# SMR.net
KiCad netlist of a schematic drawn in EAGLE
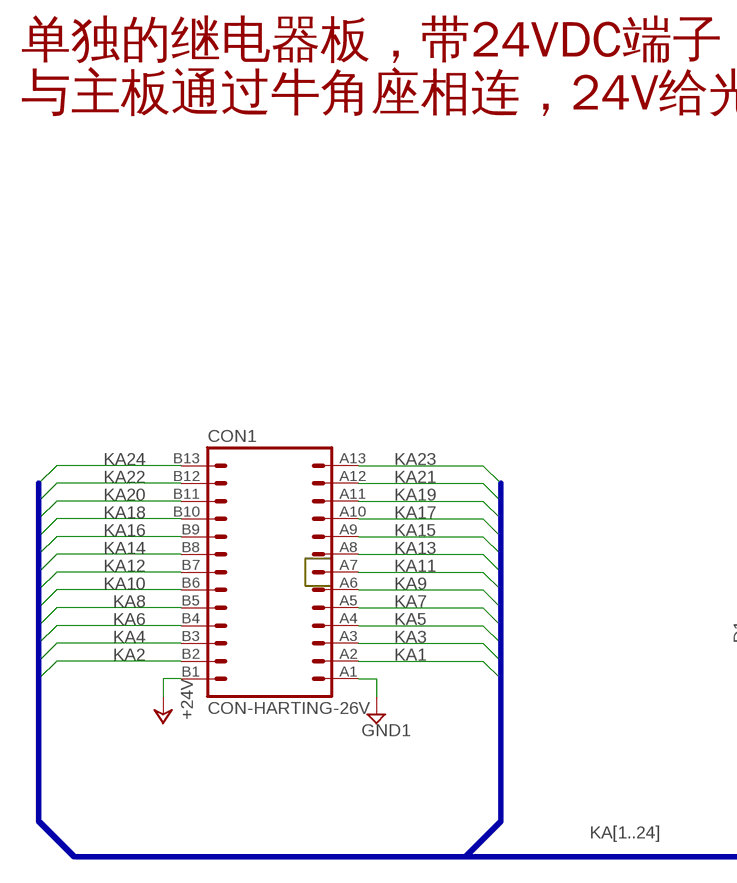
[diagram p0: schematic, sheet 1, part 1 of 2]
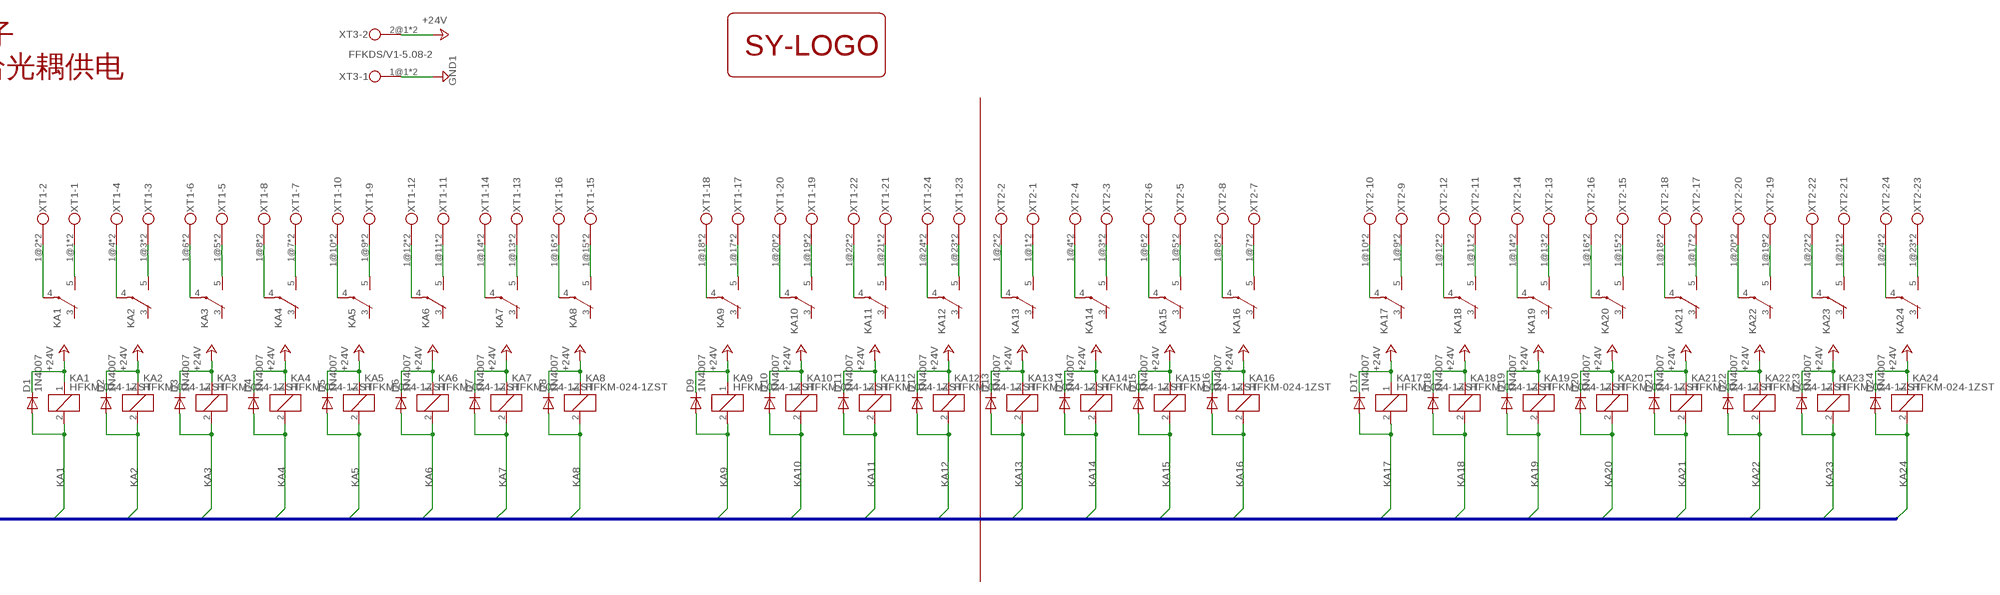
[diagram p1: schematic, sheet 1, part 2 of 2]

(export (version "E")
  (design (tool "Eeschema 10.0.6"))
  (components
    (comp (ref "CON1")
      (value "CON-HARTING-26V")
      (footprint "eagle-import:26V")
      (libsource (lib "eagle-import") (part "CON-HARTING-26V"))
    )
    (comp (ref "D1")
      (value "1N4007")
      (footprint "eagle-import:DO41-10")
      (libsource (lib "eagle-import") (part "1N4007"))
    )
    (comp (ref "D2")
      (value "1N4007")
      (footprint "eagle-import:DO41-10")
      (libsource (lib "eagle-import") (part "1N4007"))
    )
    (comp (ref "D3")
      (value "1N4007")
      (footprint "eagle-import:DO41-10")
      (libsource (lib "eagle-import") (part "1N4007"))
    )
    (comp (ref "D4")
      (value "1N4007")
      (footprint "eagle-import:DO41-10")
      (libsource (lib "eagle-import") (part "1N4007"))
    )
    (comp (ref "D5")
      (value "1N4007")
      (footprint "eagle-import:DO41-10")
      (libsource (lib "eagle-import") (part "1N4007"))
    )
    (comp (ref "D6")
      (value "1N4007")
      (footprint "eagle-import:DO41-10")
      (libsource (lib "eagle-import") (part "1N4007"))
    )
    (comp (ref "D7")
      (value "1N4007")
      (footprint "eagle-import:DO41-10")
      (libsource (lib "eagle-import") (part "1N4007"))
    )
    (comp (ref "D8")
      (value "1N4007")
      (footprint "eagle-import:DO41-10")
      (libsource (lib "eagle-import") (part "1N4007"))
    )
    (comp (ref "D9")
      (value "1N4007")
      (footprint "eagle-import:DO41-10")
      (libsource (lib "eagle-import") (part "1N4007"))
    )
    (comp (ref "D10")
      (value "1N4007")
      (footprint "eagle-import:DO41-10")
      (libsource (lib "eagle-import") (part "1N4007"))
    )
    (comp (ref "D11")
      (value "1N4007")
      (footprint "eagle-import:DO41-10")
      (libsource (lib "eagle-import") (part "1N4007"))
    )
    (comp (ref "D12")
      (value "1N4007")
      (footprint "eagle-import:DO41-10")
      (libsource (lib "eagle-import") (part "1N4007"))
    )
    (comp (ref "D13")
      (value "1N4007")
      (footprint "eagle-import:DO41-10")
      (libsource (lib "eagle-import") (part "1N4007"))
    )
    (comp (ref "D14")
      (value "1N4007")
      (footprint "eagle-import:DO41-10")
      (libsource (lib "eagle-import") (part "1N4007"))
    )
    (comp (ref "D15")
      (value "1N4007")
      (footprint "eagle-import:DO41-10")
      (libsource (lib "eagle-import") (part "1N4007"))
    )
    (comp (ref "D16")
      (value "1N4007")
      (footprint "eagle-import:DO41-10")
      (libsource (lib "eagle-import") (part "1N4007"))
    )
    (comp (ref "D17")
      (value "1N4007")
      (footprint "eagle-import:DO41-10")
      (libsource (lib "eagle-import") (part "1N4007"))
    )
    (comp (ref "D18")
      (value "1N4007")
      (footprint "eagle-import:DO41-10")
      (libsource (lib "eagle-import") (part "1N4007"))
    )
    (comp (ref "D19")
      (value "1N4007")
      (footprint "eagle-import:DO41-10")
      (libsource (lib "eagle-import") (part "1N4007"))
    )
    (comp (ref "D20")
      (value "1N4007")
      (footprint "eagle-import:DO41-10")
      (libsource (lib "eagle-import") (part "1N4007"))
    )
    (comp (ref "D21")
      (value "1N4007")
      (footprint "eagle-import:DO41-10")
      (libsource (lib "eagle-import") (part "1N4007"))
    )
    (comp (ref "D22")
      (value "1N4007")
      (footprint "eagle-import:DO41-10")
      (libsource (lib "eagle-import") (part "1N4007"))
    )
    (comp (ref "D23")
      (value "1N4007")
      (footprint "eagle-import:DO41-10")
      (libsource (lib "eagle-import") (part "1N4007"))
    )
    (comp (ref "D24")
      (value "1N4007")
      (footprint "eagle-import:DO41-10")
      (libsource (lib "eagle-import") (part "1N4007"))
    )
    (comp (ref "KA1")
      (value "HFKM-024-1ZST")
      (footprint "eagle-import:HFKM-1ZST")
      (libsource (lib "eagle-import") (part "HFKM-024-1ZST"))
    )
    (comp (ref "KA2")
      (value "HFKM-024-1ZST")
      (footprint "eagle-import:HFKM-1ZST")
      (libsource (lib "eagle-import") (part "HFKM-024-1ZST"))
    )
    (comp (ref "KA3")
      (value "HFKM-024-1ZST")
      (footprint "eagle-import:HFKM-1ZST")
      (libsource (lib "eagle-import") (part "HFKM-024-1ZST"))
    )
    (comp (ref "KA4")
      (value "HFKM-024-1ZST")
      (footprint "eagle-import:HFKM-1ZST")
      (libsource (lib "eagle-import") (part "HFKM-024-1ZST"))
    )
    (comp (ref "KA5")
      (value "HFKM-024-1ZST")
      (footprint "eagle-import:HFKM-1ZST")
      (libsource (lib "eagle-import") (part "HFKM-024-1ZST"))
    )
    (comp (ref "KA6")
      (value "HFKM-024-1ZST")
      (footprint "eagle-import:HFKM-1ZST")
      (libsource (lib "eagle-import") (part "HFKM-024-1ZST"))
    )
    (comp (ref "KA7")
      (value "HFKM-024-1ZST")
      (footprint "eagle-import:HFKM-1ZST")
      (libsource (lib "eagle-import") (part "HFKM-024-1ZST"))
    )
    (comp (ref "KA8")
      (value "HFKM-024-1ZST")
      (footprint "eagle-import:HFKM-1ZST")
      (libsource (lib "eagle-import") (part "HFKM-024-1ZST"))
    )
    (comp (ref "KA9")
      (value "HFKM-024-1ZST")
      (footprint "eagle-import:HFKM-1ZST")
      (libsource (lib "eagle-import") (part "HFKM-024-1ZST"))
    )
    (comp (ref "KA10")
      (value "HFKM-024-1ZST")
      (footprint "eagle-import:HFKM-1ZST")
      (libsource (lib "eagle-import") (part "HFKM-024-1ZST"))
    )
    (comp (ref "KA11")
      (value "HFKM-024-1ZST")
      (footprint "eagle-import:HFKM-1ZST")
      (libsource (lib "eagle-import") (part "HFKM-024-1ZST"))
    )
    (comp (ref "KA12")
      (value "HFKM-024-1ZST")
      (footprint "eagle-import:HFKM-1ZST")
      (libsource (lib "eagle-import") (part "HFKM-024-1ZST"))
    )
    (comp (ref "KA13")
      (value "HFKM-024-1ZST")
      (footprint "eagle-import:HFKM-1ZST")
      (libsource (lib "eagle-import") (part "HFKM-024-1ZST"))
    )
    (comp (ref "KA14")
      (value "HFKM-024-1ZST")
      (footprint "eagle-import:HFKM-1ZST")
      (libsource (lib "eagle-import") (part "HFKM-024-1ZST"))
    )
    (comp (ref "KA15")
      (value "HFKM-024-1ZST")
      (footprint "eagle-import:HFKM-1ZST")
      (libsource (lib "eagle-import") (part "HFKM-024-1ZST"))
    )
    (comp (ref "KA16")
      (value "HFKM-024-1ZST")
      (footprint "eagle-import:HFKM-1ZST")
      (libsource (lib "eagle-import") (part "HFKM-024-1ZST"))
    )
    (comp (ref "KA17")
      (value "HFKM-024-1ZST")
      (footprint "eagle-import:HFKM-1ZST")
      (libsource (lib "eagle-import") (part "HFKM-024-1ZST"))
    )
    (comp (ref "KA18")
      (value "HFKM-024-1ZST")
      (footprint "eagle-import:HFKM-1ZST")
      (libsource (lib "eagle-import") (part "HFKM-024-1ZST"))
    )
    (comp (ref "KA19")
      (value "HFKM-024-1ZST")
      (footprint "eagle-import:HFKM-1ZST")
      (libsource (lib "eagle-import") (part "HFKM-024-1ZST"))
    )
    (comp (ref "KA20")
      (value "HFKM-024-1ZST")
      (footprint "eagle-import:HFKM-1ZST")
      (libsource (lib "eagle-import") (part "HFKM-024-1ZST"))
    )
    (comp (ref "KA21")
      (value "HFKM-024-1ZST")
      (footprint "eagle-import:HFKM-1ZST")
      (libsource (lib "eagle-import") (part "HFKM-024-1ZST"))
    )
    (comp (ref "KA22")
      (value "HFKM-024-1ZST")
      (footprint "eagle-import:HFKM-1ZST")
      (libsource (lib "eagle-import") (part "HFKM-024-1ZST"))
    )
    (comp (ref "KA23")
      (value "HFKM-024-1ZST")
      (footprint "eagle-import:HFKM-1ZST")
      (libsource (lib "eagle-import") (part "HFKM-024-1ZST"))
    )
    (comp (ref "KA24")
      (value "HFKM-024-1ZST")
      (footprint "eagle-import:HFKM-1ZST")
      (libsource (lib "eagle-import") (part "HFKM-024-1ZST"))
    )
    (comp (ref "LOGO1")
      (value "SY-LOGO_BOTTOM")
      (footprint "eagle-import:SY-LOGO_BOTTOM")
      (libsource (lib "eagle-import") (part "SY-LOGO_BOTTOM"))
    )
    (comp (ref "XT1")
      (value "FFKDS/V1-5.08-24")
      (footprint "eagle-import:FFKDS_V1-5.08-24")
      (libsource (lib "eagle-import") (part "FFKDS/V1-5.08-24"))
    )
    (comp (ref "XT2")
      (value "FFKDS/V1-5.08-24")
      (footprint "eagle-import:FFKDS_V1-5.08-24")
      (libsource (lib "eagle-import") (part "FFKDS/V1-5.08-24"))
    )
    (comp (ref "XT3")
      (value "FFKDS/V1-5.08-2")
      (footprint "eagle-import:FFKDS_V1-5.08-2")
      (libsource (lib "eagle-import") (part "FFKDS/V1-5.08-2"))
    )
  )
  (nets
    (net (code "1") (name "+24V") (class "Default")
      (node (ref "CON1") (pin "B1") (pinfunction "B1_B1") (pintype "passive"))
      (node (ref "D1") (pin "C") (pinfunction "C_C") (pintype "passive"))
      (node (ref "D10") (pin "C") (pinfunction "C_C") (pintype "passive"))
      (node (ref "D11") (pin "C") (pinfunction "C_C") (pintype "passive"))
      (node (ref "D12") (pin "C") (pinfunction "C_C") (pintype "passive"))
      (node (ref "D13") (pin "C") (pinfunction "C_C") (pintype "passive"))
      (node (ref "D14") (pin "C") (pinfunction "C_C") (pintype "passive"))
      (node (ref "D15") (pin "C") (pinfunction "C_C") (pintype "passive"))
      (node (ref "D16") (pin "C") (pinfunction "C_C") (pintype "passive"))
      (node (ref "D17") (pin "C") (pinfunction "C_C") (pintype "passive"))
      (node (ref "D18") (pin "C") (pinfunction "C_C") (pintype "passive"))
      (node (ref "D19") (pin "C") (pinfunction "C_C") (pintype "passive"))
      (node (ref "D2") (pin "C") (pinfunction "C_C") (pintype "passive"))
      (node (ref "D20") (pin "C") (pinfunction "C_C") (pintype "passive"))
      (node (ref "D21") (pin "C") (pinfunction "C_C") (pintype "passive"))
      (node (ref "D22") (pin "C") (pinfunction "C_C") (pintype "passive"))
      (node (ref "D23") (pin "C") (pinfunction "C_C") (pintype "passive"))
      (node (ref "D24") (pin "C") (pinfunction "C_C") (pintype "passive"))
      (node (ref "D3") (pin "C") (pinfunction "C_C") (pintype "passive"))
      (node (ref "D4") (pin "C") (pinfunction "C_C") (pintype "passive"))
      (node (ref "D5") (pin "C") (pinfunction "C_C") (pintype "passive"))
      (node (ref "D6") (pin "C") (pinfunction "C_C") (pintype "passive"))
      (node (ref "D7") (pin "C") (pinfunction "C_C") (pintype "passive"))
      (node (ref "D8") (pin "C") (pinfunction "C_C") (pintype "passive"))
      (node (ref "D9") (pin "C") (pinfunction "C_C") (pintype "passive"))
      (node (ref "KA1") (pin "1") (pinfunction "COIL1_1") (pintype "passive"))
      (node (ref "KA10") (pin "1") (pinfunction "COIL1_1") (pintype "passive"))
      (node (ref "KA11") (pin "1") (pinfunction "COIL1_1") (pintype "passive"))
      (node (ref "KA12") (pin "1") (pinfunction "COIL1_1") (pintype "passive"))
      (node (ref "KA13") (pin "1") (pinfunction "COIL1_1") (pintype "passive"))
      (node (ref "KA14") (pin "1") (pinfunction "COIL1_1") (pintype "passive"))
      (node (ref "KA15") (pin "1") (pinfunction "COIL1_1") (pintype "passive"))
      (node (ref "KA16") (pin "1") (pinfunction "COIL1_1") (pintype "passive"))
      (node (ref "KA17") (pin "1") (pinfunction "COIL1_1") (pintype "passive"))
      (node (ref "KA18") (pin "1") (pinfunction "COIL1_1") (pintype "passive"))
      (node (ref "KA19") (pin "1") (pinfunction "COIL1_1") (pintype "passive"))
      (node (ref "KA2") (pin "1") (pinfunction "COIL1_1") (pintype "passive"))
      (node (ref "KA20") (pin "1") (pinfunction "COIL1_1") (pintype "passive"))
      (node (ref "KA21") (pin "1") (pinfunction "COIL1_1") (pintype "passive"))
      (node (ref "KA22") (pin "1") (pinfunction "COIL1_1") (pintype "passive"))
      (node (ref "KA23") (pin "1") (pinfunction "COIL1_1") (pintype "passive"))
      (node (ref "KA24") (pin "1") (pinfunction "COIL1_1") (pintype "passive"))
      (node (ref "KA3") (pin "1") (pinfunction "COIL1_1") (pintype "passive"))
      (node (ref "KA4") (pin "1") (pinfunction "COIL1_1") (pintype "passive"))
      (node (ref "KA5") (pin "1") (pinfunction "COIL1_1") (pintype "passive"))
      (node (ref "KA6") (pin "1") (pinfunction "COIL1_1") (pintype "passive"))
      (node (ref "KA7") (pin "1") (pinfunction "COIL1_1") (pintype "passive"))
      (node (ref "KA8") (pin "1") (pinfunction "COIL1_1") (pintype "passive"))
      (node (ref "KA9") (pin "1") (pinfunction "COIL1_1") (pintype "passive"))
      (node (ref "XT3") (pin "2@1") (pinfunction "1_2@1") (pintype "passive"))
      (node (ref "XT3") (pin "2@2") (pinfunction "1_2@2") (pintype "passive"))
    )
    (net (code "2") (name "/KA1") (class "Default")
      (node (ref "CON1") (pin "A2") (pinfunction "A2_A2") (pintype "passive"))
      (node (ref "D1") (pin "A") (pinfunction "A_A") (pintype "passive"))
      (node (ref "KA1") (pin "2") (pinfunction "COIL2_2") (pintype "passive"))
    )
    (net (code "3") (name "/KA2") (class "Default")
      (node (ref "CON1") (pin "B2") (pinfunction "B2_B2") (pintype "passive"))
      (node (ref "D2") (pin "A") (pinfunction "A_A") (pintype "passive"))
      (node (ref "KA2") (pin "2") (pinfunction "COIL2_2") (pintype "passive"))
    )
    (net (code "4") (name "/KA3") (class "Default")
      (node (ref "CON1") (pin "A3") (pinfunction "A3_A3") (pintype "passive"))
      (node (ref "D3") (pin "A") (pinfunction "A_A") (pintype "passive"))
      (node (ref "KA3") (pin "2") (pinfunction "COIL2_2") (pintype "passive"))
    )
    (net (code "5") (name "/KA4") (class "Default")
      (node (ref "CON1") (pin "B3") (pinfunction "B3_B3") (pintype "passive"))
      (node (ref "D4") (pin "A") (pinfunction "A_A") (pintype "passive"))
      (node (ref "KA4") (pin "2") (pinfunction "COIL2_2") (pintype "passive"))
    )
    (net (code "6") (name "/KA5") (class "Default")
      (node (ref "CON1") (pin "A4") (pinfunction "A4_A4") (pintype "passive"))
      (node (ref "D5") (pin "A") (pinfunction "A_A") (pintype "passive"))
      (node (ref "KA5") (pin "2") (pinfunction "COIL2_2") (pintype "passive"))
    )
    (net (code "7") (name "/KA6") (class "Default")
      (node (ref "CON1") (pin "B4") (pinfunction "B4_B4") (pintype "passive"))
      (node (ref "D6") (pin "A") (pinfunction "A_A") (pintype "passive"))
      (node (ref "KA6") (pin "2") (pinfunction "COIL2_2") (pintype "passive"))
    )
    (net (code "8") (name "/KA7") (class "Default")
      (node (ref "CON1") (pin "A5") (pinfunction "A5_A5") (pintype "passive"))
      (node (ref "D7") (pin "A") (pinfunction "A_A") (pintype "passive"))
      (node (ref "KA7") (pin "2") (pinfunction "COIL2_2") (pintype "passive"))
    )
    (net (code "9") (name "/KA8") (class "Default")
      (node (ref "CON1") (pin "B5") (pinfunction "B5_B5") (pintype "passive"))
      (node (ref "D8") (pin "A") (pinfunction "A_A") (pintype "passive"))
      (node (ref "KA8") (pin "2") (pinfunction "COIL2_2") (pintype "passive"))
    )
    (net (code "10") (name "/KA9") (class "Default")
      (node (ref "CON1") (pin "A6") (pinfunction "A6_A6") (pintype "passive"))
      (node (ref "D9") (pin "A") (pinfunction "A_A") (pintype "passive"))
      (node (ref "KA9") (pin "2") (pinfunction "COIL2_2") (pintype "passive"))
    )
    (net (code "11") (name "/KA10") (class "Default")
      (node (ref "CON1") (pin "B6") (pinfunction "B6_B6") (pintype "passive"))
      (node (ref "D10") (pin "A") (pinfunction "A_A") (pintype "passive"))
      (node (ref "KA10") (pin "2") (pinfunction "COIL2_2") (pintype "passive"))
    )
    (net (code "12") (name "/KA11") (class "Default")
      (node (ref "CON1") (pin "A7") (pinfunction "A7_A7") (pintype "passive"))
      (node (ref "D11") (pin "A") (pinfunction "A_A") (pintype "passive"))
      (node (ref "KA11") (pin "2") (pinfunction "COIL2_2") (pintype "passive"))
    )
    (net (code "13") (name "/KA12") (class "Default")
      (node (ref "CON1") (pin "B7") (pinfunction "B7_B7") (pintype "passive"))
      (node (ref "D12") (pin "A") (pinfunction "A_A") (pintype "passive"))
      (node (ref "KA12") (pin "2") (pinfunction "COIL2_2") (pintype "passive"))
    )
    (net (code "14") (name "/KA13") (class "Default")
      (node (ref "CON1") (pin "A8") (pinfunction "A8_A8") (pintype "passive"))
      (node (ref "D13") (pin "A") (pinfunction "A_A") (pintype "passive"))
      (node (ref "KA13") (pin "2") (pinfunction "COIL2_2") (pintype "passive"))
    )
    (net (code "15") (name "/KA14") (class "Default")
      (node (ref "CON1") (pin "B8") (pinfunction "B8_B8") (pintype "passive"))
      (node (ref "D14") (pin "A") (pinfunction "A_A") (pintype "passive"))
      (node (ref "KA14") (pin "2") (pinfunction "COIL2_2") (pintype "passive"))
    )
    (net (code "16") (name "/KA15") (class "Default")
      (node (ref "CON1") (pin "A9") (pinfunction "A9_A9") (pintype "passive"))
      (node (ref "D15") (pin "A") (pinfunction "A_A") (pintype "passive"))
      (node (ref "KA15") (pin "2") (pinfunction "COIL2_2") (pintype "passive"))
    )
    (net (code "17") (name "/KA16") (class "Default")
      (node (ref "CON1") (pin "B9") (pinfunction "B9_B9") (pintype "passive"))
      (node (ref "D16") (pin "A") (pinfunction "A_A") (pintype "passive"))
      (node (ref "KA16") (pin "2") (pinfunction "COIL2_2") (pintype "passive"))
    )
    (net (code "18") (name "/KA17") (class "Default")
      (node (ref "CON1") (pin "A10") (pinfunction "A10_A10") (pintype "passive"))
      (node (ref "D17") (pin "A") (pinfunction "A_A") (pintype "passive"))
      (node (ref "KA17") (pin "2") (pinfunction "COIL2_2") (pintype "passive"))
    )
    (net (code "19") (name "/KA18") (class "Default")
      (node (ref "CON1") (pin "B10") (pinfunction "B10_B10") (pintype "passive"))
      (node (ref "D18") (pin "A") (pinfunction "A_A") (pintype "passive"))
      (node (ref "KA18") (pin "2") (pinfunction "COIL2_2") (pintype "passive"))
    )
    (net (code "20") (name "/KA19") (class "Default")
      (node (ref "CON1") (pin "A11") (pinfunction "A11_A11") (pintype "passive"))
      (node (ref "D19") (pin "A") (pinfunction "A_A") (pintype "passive"))
      (node (ref "KA19") (pin "2") (pinfunction "COIL2_2") (pintype "passive"))
    )
    (net (code "21") (name "/KA20") (class "Default")
      (node (ref "CON1") (pin "B11") (pinfunction "B11_B11") (pintype "passive"))
      (node (ref "D20") (pin "A") (pinfunction "A_A") (pintype "passive"))
      (node (ref "KA20") (pin "2") (pinfunction "COIL2_2") (pintype "passive"))
    )
    (net (code "22") (name "/KA21") (class "Default")
      (node (ref "CON1") (pin "A12") (pinfunction "A12_A12") (pintype "passive"))
      (node (ref "D21") (pin "A") (pinfunction "A_A") (pintype "passive"))
      (node (ref "KA21") (pin "2") (pinfunction "COIL2_2") (pintype "passive"))
    )
    (net (code "23") (name "/KA22") (class "Default")
      (node (ref "CON1") (pin "B12") (pinfunction "B12_B12") (pintype "passive"))
      (node (ref "D22") (pin "A") (pinfunction "A_A") (pintype "passive"))
      (node (ref "KA22") (pin "2") (pinfunction "COIL2_2") (pintype "passive"))
    )
    (net (code "24") (name "/KA23") (class "Default")
      (node (ref "CON1") (pin "A13") (pinfunction "A13_A13") (pintype "passive"))
      (node (ref "D23") (pin "A") (pinfunction "A_A") (pintype "passive"))
      (node (ref "KA23") (pin "2") (pinfunction "COIL2_2") (pintype "passive"))
    )
    (net (code "25") (name "/KA24") (class "Default")
      (node (ref "CON1") (pin "B13") (pinfunction "B13_B13") (pintype "passive"))
      (node (ref "D24") (pin "A") (pinfunction "A_A") (pintype "passive"))
      (node (ref "KA24") (pin "2") (pinfunction "COIL2_2") (pintype "passive"))
    )
    (net (code "27") (name "GND1") (class "Default")
      (node (ref "CON1") (pin "A1") (pinfunction "A1_A1") (pintype "passive"))
      (node (ref "XT3") (pin "1@1") (pinfunction "1_1@1") (pintype "passive"))
      (node (ref "XT3") (pin "1@2") (pinfunction "1_1@2") (pintype "passive"))
    )
    (net (code "28") (name "Net-(KA1B-COM)") (class "Default")
      (node (ref "KA1") (pin "4") (pinfunction "COM_4") (pintype "passive"))
      (node (ref "XT1") (pin "1@2") (pinfunction "1_1@2") (pintype "passive"))
      (node (ref "XT1") (pin "2@2") (pinfunction "1_2@2") (pintype "passive"))
    )
    (net (code "29") (name "Net-(KA1B-NO)") (class "Default")
      (node (ref "KA1") (pin "5") (pinfunction "NO_5") (pintype "passive"))
      (node (ref "XT1") (pin "1@1") (pinfunction "1_1@1") (pintype "passive"))
      (node (ref "XT1") (pin "2@1") (pinfunction "1_2@1") (pintype "passive"))
    )
    (net (code "30") (name "Net-(KA2B-COM)") (class "Default")
      (node (ref "KA2") (pin "4") (pinfunction "COM_4") (pintype "passive"))
      (node (ref "XT1") (pin "1@4") (pinfunction "1_1@4") (pintype "passive"))
      (node (ref "XT1") (pin "2@4") (pinfunction "1_2@4") (pintype "passive"))
    )
    (net (code "31") (name "Net-(KA2B-NO)") (class "Default")
      (node (ref "KA2") (pin "5") (pinfunction "NO_5") (pintype "passive"))
      (node (ref "XT1") (pin "1@3") (pinfunction "1_1@3") (pintype "passive"))
      (node (ref "XT1") (pin "2@3") (pinfunction "1_2@3") (pintype "passive"))
    )
    (net (code "32") (name "Net-(KA3B-COM)") (class "Default")
      (node (ref "KA3") (pin "4") (pinfunction "COM_4") (pintype "passive"))
      (node (ref "XT1") (pin "1@6") (pinfunction "1_1@6") (pintype "passive"))
      (node (ref "XT1") (pin "2@6") (pinfunction "1_2@6") (pintype "passive"))
    )
    (net (code "33") (name "Net-(KA3B-NO)") (class "Default")
      (node (ref "KA3") (pin "5") (pinfunction "NO_5") (pintype "passive"))
      (node (ref "XT1") (pin "1@5") (pinfunction "1_1@5") (pintype "passive"))
      (node (ref "XT1") (pin "2@5") (pinfunction "1_2@5") (pintype "passive"))
    )
    (net (code "34") (name "Net-(KA4B-COM)") (class "Default")
      (node (ref "KA4") (pin "4") (pinfunction "COM_4") (pintype "passive"))
      (node (ref "XT1") (pin "1@8") (pinfunction "1_1@8") (pintype "passive"))
      (node (ref "XT1") (pin "2@8") (pinfunction "1_2@8") (pintype "passive"))
    )
    (net (code "35") (name "Net-(KA4B-NO)") (class "Default")
      (node (ref "KA4") (pin "5") (pinfunction "NO_5") (pintype "passive"))
      (node (ref "XT1") (pin "1@7") (pinfunction "1_1@7") (pintype "passive"))
      (node (ref "XT1") (pin "2@7") (pinfunction "1_2@7") (pintype "passive"))
    )
    (net (code "36") (name "Net-(KA5B-COM)") (class "Default")
      (node (ref "KA5") (pin "4") (pinfunction "COM_4") (pintype "passive"))
      (node (ref "XT1") (pin "1@10") (pinfunction "1_1@10") (pintype "passive"))
      (node (ref "XT1") (pin "2@10") (pinfunction "1_2@10") (pintype "passive"))
    )
    (net (code "37") (name "Net-(KA5B-NO)") (class "Default")
      (node (ref "KA5") (pin "5") (pinfunction "NO_5") (pintype "passive"))
      (node (ref "XT1") (pin "1@9") (pinfunction "1_1@9") (pintype "passive"))
      (node (ref "XT1") (pin "2@9") (pinfunction "1_2@9") (pintype "passive"))
    )
    (net (code "38") (name "Net-(KA6B-COM)") (class "Default")
      (node (ref "KA6") (pin "4") (pinfunction "COM_4") (pintype "passive"))
      (node (ref "XT1") (pin "1@12") (pinfunction "1_1@12") (pintype "passive"))
      (node (ref "XT1") (pin "2@12") (pinfunction "1_2@12") (pintype "passive"))
    )
    (net (code "39") (name "Net-(KA6B-NO)") (class "Default")
      (node (ref "KA6") (pin "5") (pinfunction "NO_5") (pintype "passive"))
      (node (ref "XT1") (pin "1@11") (pinfunction "1_1@11") (pintype "passive"))
      (node (ref "XT1") (pin "2@11") (pinfunction "1_2@11") (pintype "passive"))
    )
    (net (code "40") (name "Net-(KA7B-COM)") (class "Default")
      (node (ref "KA7") (pin "4") (pinfunction "COM_4") (pintype "passive"))
      (node (ref "XT1") (pin "1@14") (pinfunction "1_1@14") (pintype "passive"))
      (node (ref "XT1") (pin "2@14") (pinfunction "1_2@14") (pintype "passive"))
    )
    (net (code "41") (name "Net-(KA7B-NO)") (class "Default")
      (node (ref "KA7") (pin "5") (pinfunction "NO_5") (pintype "passive"))
      (node (ref "XT1") (pin "1@13") (pinfunction "1_1@13") (pintype "passive"))
      (node (ref "XT1") (pin "2@13") (pinfunction "1_2@13") (pintype "passive"))
    )
    (net (code "42") (name "Net-(KA8B-COM)") (class "Default")
      (node (ref "KA8") (pin "4") (pinfunction "COM_4") (pintype "passive"))
      (node (ref "XT1") (pin "1@16") (pinfunction "1_1@16") (pintype "passive"))
      (node (ref "XT1") (pin "2@16") (pinfunction "1_2@16") (pintype "passive"))
    )
    (net (code "43") (name "Net-(KA8B-NO)") (class "Default")
      (node (ref "KA8") (pin "5") (pinfunction "NO_5") (pintype "passive"))
      (node (ref "XT1") (pin "1@15") (pinfunction "1_1@15") (pintype "passive"))
      (node (ref "XT1") (pin "2@15") (pinfunction "1_2@15") (pintype "passive"))
    )
    (net (code "44") (name "Net-(KA9B-COM)") (class "Default")
      (node (ref "KA9") (pin "4") (pinfunction "COM_4") (pintype "passive"))
      (node (ref "XT1") (pin "1@18") (pinfunction "1_1@18") (pintype "passive"))
      (node (ref "XT1") (pin "2@18") (pinfunction "1_2@18") (pintype "passive"))
    )
    (net (code "45") (name "Net-(KA9B-NO)") (class "Default")
      (node (ref "KA9") (pin "5") (pinfunction "NO_5") (pintype "passive"))
      (node (ref "XT1") (pin "1@17") (pinfunction "1_1@17") (pintype "passive"))
      (node (ref "XT1") (pin "2@17") (pinfunction "1_2@17") (pintype "passive"))
    )
    (net (code "46") (name "Net-(KA10B-COM)") (class "Default")
      (node (ref "KA10") (pin "4") (pinfunction "COM_4") (pintype "passive"))
      (node (ref "XT1") (pin "1@20") (pinfunction "1_1@20") (pintype "passive"))
      (node (ref "XT1") (pin "2@20") (pinfunction "1_2@20") (pintype "passive"))
    )
    (net (code "47") (name "Net-(KA10B-NO)") (class "Default")
      (node (ref "KA10") (pin "5") (pinfunction "NO_5") (pintype "passive"))
      (node (ref "XT1") (pin "1@19") (pinfunction "1_1@19") (pintype "passive"))
      (node (ref "XT1") (pin "2@19") (pinfunction "1_2@19") (pintype "passive"))
    )
    (net (code "48") (name "Net-(KA11B-COM)") (class "Default")
      (node (ref "KA11") (pin "4") (pinfunction "COM_4") (pintype "passive"))
      (node (ref "XT1") (pin "1@22") (pinfunction "1_1@22") (pintype "passive"))
      (node (ref "XT1") (pin "2@22") (pinfunction "1_2@22") (pintype "passive"))
    )
    (net (code "49") (name "Net-(KA11B-NO)") (class "Default")
      (node (ref "KA11") (pin "5") (pinfunction "NO_5") (pintype "passive"))
      (node (ref "XT1") (pin "1@21") (pinfunction "1_1@21") (pintype "passive"))
      (node (ref "XT1") (pin "2@21") (pinfunction "1_2@21") (pintype "passive"))
    )
    (net (code "50") (name "Net-(KA12B-COM)") (class "Default")
      (node (ref "KA12") (pin "4") (pinfunction "COM_4") (pintype "passive"))
      (node (ref "XT1") (pin "1@24") (pinfunction "1_1@24") (pintype "passive"))
      (node (ref "XT1") (pin "2@24") (pinfunction "1_2@24") (pintype "passive"))
    )
    (net (code "51") (name "Net-(KA12B-NO)") (class "Default")
      (node (ref "KA12") (pin "5") (pinfunction "NO_5") (pintype "passive"))
      (node (ref "XT1") (pin "1@23") (pinfunction "1_1@23") (pintype "passive"))
      (node (ref "XT1") (pin "2@23") (pinfunction "1_2@23") (pintype "passive"))
    )
    (net (code "52") (name "Net-(KA13B-COM)") (class "Default")
      (node (ref "KA13") (pin "4") (pinfunction "COM_4") (pintype "passive"))
      (node (ref "XT2") (pin "1@2") (pinfunction "1_1@2") (pintype "passive"))
      (node (ref "XT2") (pin "2@2") (pinfunction "1_2@2") (pintype "passive"))
    )
    (net (code "53") (name "Net-(KA13B-NO)") (class "Default")
      (node (ref "KA13") (pin "5") (pinfunction "NO_5") (pintype "passive"))
      (node (ref "XT2") (pin "1@1") (pinfunction "1_1@1") (pintype "passive"))
      (node (ref "XT2") (pin "2@1") (pinfunction "1_2@1") (pintype "passive"))
    )
    (net (code "54") (name "Net-(KA14B-COM)") (class "Default")
      (node (ref "KA14") (pin "4") (pinfunction "COM_4") (pintype "passive"))
      (node (ref "XT2") (pin "1@4") (pinfunction "1_1@4") (pintype "passive"))
      (node (ref "XT2") (pin "2@4") (pinfunction "1_2@4") (pintype "passive"))
    )
    (net (code "55") (name "Net-(KA14B-NO)") (class "Default")
      (node (ref "KA14") (pin "5") (pinfunction "NO_5") (pintype "passive"))
      (node (ref "XT2") (pin "1@3") (pinfunction "1_1@3") (pintype "passive"))
      (node (ref "XT2") (pin "2@3") (pinfunction "1_2@3") (pintype "passive"))
    )
    (net (code "56") (name "Net-(KA15B-COM)") (class "Default")
      (node (ref "KA15") (pin "4") (pinfunction "COM_4") (pintype "passive"))
      (node (ref "XT2") (pin "1@6") (pinfunction "1_1@6") (pintype "passive"))
      (node (ref "XT2") (pin "2@6") (pinfunction "1_2@6") (pintype "passive"))
    )
    (net (code "57") (name "Net-(KA15B-NO)") (class "Default")
      (node (ref "KA15") (pin "5") (pinfunction "NO_5") (pintype "passive"))
      (node (ref "XT2") (pin "1@5") (pinfunction "1_1@5") (pintype "passive"))
      (node (ref "XT2") (pin "2@5") (pinfunction "1_2@5") (pintype "passive"))
    )
    (net (code "58") (name "Net-(KA16B-COM)") (class "Default")
      (node (ref "KA16") (pin "4") (pinfunction "COM_4") (pintype "passive"))
      (node (ref "XT2") (pin "1@8") (pinfunction "1_1@8") (pintype "passive"))
      (node (ref "XT2") (pin "2@8") (pinfunction "1_2@8") (pintype "passive"))
    )
    (net (code "59") (name "Net-(KA16B-NO)") (class "Default")
      (node (ref "KA16") (pin "5") (pinfunction "NO_5") (pintype "passive"))
      (node (ref "XT2") (pin "1@7") (pinfunction "1_1@7") (pintype "passive"))
      (node (ref "XT2") (pin "2@7") (pinfunction "1_2@7") (pintype "passive"))
    )
    (net (code "60") (name "Net-(KA17B-COM)") (class "Default")
      (node (ref "KA17") (pin "4") (pinfunction "COM_4") (pintype "passive"))
      (node (ref "XT2") (pin "1@10") (pinfunction "1_1@10") (pintype "passive"))
      (node (ref "XT2") (pin "2@10") (pinfunction "1_2@10") (pintype "passive"))
    )
    (net (code "61") (name "Net-(KA17B-NO)") (class "Default")
      (node (ref "KA17") (pin "5") (pinfunction "NO_5") (pintype "passive"))
      (node (ref "XT2") (pin "1@9") (pinfunction "1_1@9") (pintype "passive"))
      (node (ref "XT2") (pin "2@9") (pinfunction "1_2@9") (pintype "passive"))
    )
    (net (code "62") (name "Net-(KA18B-COM)") (class "Default")
      (node (ref "KA18") (pin "4") (pinfunction "COM_4") (pintype "passive"))
      (node (ref "XT2") (pin "1@12") (pinfunction "1_1@12") (pintype "passive"))
      (node (ref "XT2") (pin "2@12") (pinfunction "1_2@12") (pintype "passive"))
    )
    (net (code "63") (name "Net-(KA18B-NO)") (class "Default")
      (node (ref "KA18") (pin "5") (pinfunction "NO_5") (pintype "passive"))
      (node (ref "XT2") (pin "1@11") (pinfunction "1_1@11") (pintype "passive"))
      (node (ref "XT2") (pin "2@11") (pinfunction "1_2@11") (pintype "passive"))
    )
    (net (code "64") (name "Net-(KA19B-COM)") (class "Default")
      (node (ref "KA19") (pin "4") (pinfunction "COM_4") (pintype "passive"))
      (node (ref "XT2") (pin "1@14") (pinfunction "1_1@14") (pintype "passive"))
      (node (ref "XT2") (pin "2@14") (pinfunction "1_2@14") (pintype "passive"))
    )
    (net (code "65") (name "Net-(KA19B-NO)") (class "Default")
      (node (ref "KA19") (pin "5") (pinfunction "NO_5") (pintype "passive"))
      (node (ref "XT2") (pin "1@13") (pinfunction "1_1@13") (pintype "passive"))
      (node (ref "XT2") (pin "2@13") (pinfunction "1_2@13") (pintype "passive"))
    )
    (net (code "66") (name "Net-(KA20B-COM)") (class "Default")
      (node (ref "KA20") (pin "4") (pinfunction "COM_4") (pintype "passive"))
      (node (ref "XT2") (pin "1@16") (pinfunction "1_1@16") (pintype "passive"))
      (node (ref "XT2") (pin "2@16") (pinfunction "1_2@16") (pintype "passive"))
    )
    (net (code "67") (name "Net-(KA20B-NO)") (class "Default")
      (node (ref "KA20") (pin "5") (pinfunction "NO_5") (pintype "passive"))
      (node (ref "XT2") (pin "1@15") (pinfunction "1_1@15") (pintype "passive"))
      (node (ref "XT2") (pin "2@15") (pinfunction "1_2@15") (pintype "passive"))
    )
    (net (code "68") (name "Net-(KA21B-COM)") (class "Default")
      (node (ref "KA21") (pin "4") (pinfunction "COM_4") (pintype "passive"))
      (node (ref "XT2") (pin "1@18") (pinfunction "1_1@18") (pintype "passive"))
      (node (ref "XT2") (pin "2@18") (pinfunction "1_2@18") (pintype "passive"))
    )
    (net (code "69") (name "Net-(KA21B-NO)") (class "Default")
      (node (ref "KA21") (pin "5") (pinfunction "NO_5") (pintype "passive"))
      (node (ref "XT2") (pin "1@17") (pinfunction "1_1@17") (pintype "passive"))
      (node (ref "XT2") (pin "2@17") (pinfunction "1_2@17") (pintype "passive"))
    )
    (net (code "70") (name "Net-(KA22B-COM)") (class "Default")
      (node (ref "KA22") (pin "4") (pinfunction "COM_4") (pintype "passive"))
      (node (ref "XT2") (pin "1@20") (pinfunction "1_1@20") (pintype "passive"))
      (node (ref "XT2") (pin "2@20") (pinfunction "1_2@20") (pintype "passive"))
    )
    (net (code "71") (name "Net-(KA22B-NO)") (class "Default")
      (node (ref "KA22") (pin "5") (pinfunction "NO_5") (pintype "passive"))
      (node (ref "XT2") (pin "1@19") (pinfunction "1_1@19") (pintype "passive"))
      (node (ref "XT2") (pin "2@19") (pinfunction "1_2@19") (pintype "passive"))
    )
    (net (code "72") (name "Net-(KA23B-COM)") (class "Default")
      (node (ref "KA23") (pin "4") (pinfunction "COM_4") (pintype "passive"))
      (node (ref "XT2") (pin "1@22") (pinfunction "1_1@22") (pintype "passive"))
      (node (ref "XT2") (pin "2@22") (pinfunction "1_2@22") (pintype "passive"))
    )
    (net (code "73") (name "Net-(KA23B-NO)") (class "Default")
      (node (ref "KA23") (pin "5") (pinfunction "NO_5") (pintype "passive"))
      (node (ref "XT2") (pin "1@21") (pinfunction "1_1@21") (pintype "passive"))
      (node (ref "XT2") (pin "2@21") (pinfunction "1_2@21") (pintype "passive"))
    )
    (net (code "74") (name "Net-(KA24B-COM)") (class "Default")
      (node (ref "KA24") (pin "4") (pinfunction "COM_4") (pintype "passive"))
      (node (ref "XT2") (pin "1@24") (pinfunction "1_1@24") (pintype "passive"))
      (node (ref "XT2") (pin "2@24") (pinfunction "1_2@24") (pintype "passive"))
    )
    (net (code "75") (name "Net-(KA24B-NO)") (class "Default")
      (node (ref "KA24") (pin "5") (pinfunction "NO_5") (pintype "passive"))
      (node (ref "XT2") (pin "1@23") (pinfunction "1_1@23") (pintype "passive"))
      (node (ref "XT2") (pin "2@23") (pinfunction "1_2@23") (pintype "passive"))
    )
    (net (code "76") (name "unconnected-(KA1B-NC-Pad3)") (class "Default")
      (node (ref "KA1") (pin "3") (pinfunction "NC_3") (pintype "passive"))
    )
    (net (code "77") (name "unconnected-(KA2B-NC-Pad3)") (class "Default")
      (node (ref "KA2") (pin "3") (pinfunction "NC_3") (pintype "passive"))
    )
    (net (code "78") (name "unconnected-(KA3B-NC-Pad3)") (class "Default")
      (node (ref "KA3") (pin "3") (pinfunction "NC_3") (pintype "passive"))
    )
    (net (code "79") (name "unconnected-(KA4B-NC-Pad3)") (class "Default")
      (node (ref "KA4") (pin "3") (pinfunction "NC_3") (pintype "passive"))
    )
    (net (code "80") (name "unconnected-(KA5B-NC-Pad3)") (class "Default")
      (node (ref "KA5") (pin "3") (pinfunction "NC_3") (pintype "passive"))
    )
    (net (code "81") (name "unconnected-(KA6B-NC-Pad3)") (class "Default")
      (node (ref "KA6") (pin "3") (pinfunction "NC_3") (pintype "passive"))
    )
    (net (code "82") (name "unconnected-(KA7B-NC-Pad3)") (class "Default")
      (node (ref "KA7") (pin "3") (pinfunction "NC_3") (pintype "passive"))
    )
    (net (code "83") (name "unconnected-(KA8B-NC-Pad3)") (class "Default")
      (node (ref "KA8") (pin "3") (pinfunction "NC_3") (pintype "passive"))
    )
    (net (code "84") (name "unconnected-(KA9B-NC-Pad3)") (class "Default")
      (node (ref "KA9") (pin "3") (pinfunction "NC_3") (pintype "passive"))
    )
    (net (code "85") (name "unconnected-(KA10B-NC-Pad3)") (class "Default")
      (node (ref "KA10") (pin "3") (pinfunction "NC_3") (pintype "passive"))
    )
    (net (code "86") (name "unconnected-(KA11B-NC-Pad3)") (class "Default")
      (node (ref "KA11") (pin "3") (pinfunction "NC_3") (pintype "passive"))
    )
    (net (code "87") (name "unconnected-(KA12B-NC-Pad3)") (class "Default")
      (node (ref "KA12") (pin "3") (pinfunction "NC_3") (pintype "passive"))
    )
    (net (code "88") (name "unconnected-(KA13B-NC-Pad3)") (class "Default")
      (node (ref "KA13") (pin "3") (pinfunction "NC_3") (pintype "passive"))
    )
    (net (code "89") (name "unconnected-(KA14B-NC-Pad3)") (class "Default")
      (node (ref "KA14") (pin "3") (pinfunction "NC_3") (pintype "passive"))
    )
    (net (code "90") (name "unconnected-(KA15B-NC-Pad3)") (class "Default")
      (node (ref "KA15") (pin "3") (pinfunction "NC_3") (pintype "passive"))
    )
    (net (code "91") (name "unconnected-(KA16B-NC-Pad3)") (class "Default")
      (node (ref "KA16") (pin "3") (pinfunction "NC_3") (pintype "passive"))
    )
    (net (code "92") (name "unconnected-(KA17B-NC-Pad3)") (class "Default")
      (node (ref "KA17") (pin "3") (pinfunction "NC_3") (pintype "passive"))
    )
    (net (code "93") (name "unconnected-(KA18B-NC-Pad3)") (class "Default")
      (node (ref "KA18") (pin "3") (pinfunction "NC_3") (pintype "passive"))
    )
    (net (code "94") (name "unconnected-(KA19B-NC-Pad3)") (class "Default")
      (node (ref "KA19") (pin "3") (pinfunction "NC_3") (pintype "passive"))
    )
    (net (code "95") (name "unconnected-(KA20B-NC-Pad3)") (class "Default")
      (node (ref "KA20") (pin "3") (pinfunction "NC_3") (pintype "passive"))
    )
    (net (code "96") (name "unconnected-(KA21B-NC-Pad3)") (class "Default")
      (node (ref "KA21") (pin "3") (pinfunction "NC_3") (pintype "passive"))
    )
    (net (code "97") (name "unconnected-(KA22B-NC-Pad3)") (class "Default")
      (node (ref "KA22") (pin "3") (pinfunction "NC_3") (pintype "passive"))
    )
    (net (code "98") (name "unconnected-(KA23B-NC-Pad3)") (class "Default")
      (node (ref "KA23") (pin "3") (pinfunction "NC_3") (pintype "passive"))
    )
    (net (code "99") (name "unconnected-(KA24B-NC-Pad3)") (class "Default")
      (node (ref "KA24") (pin "3") (pinfunction "NC_3") (pintype "passive"))
    )
  )
)
